# Adafruit_NeoJewel_7.net
KiCad netlist of a schematic drawn in EAGLE
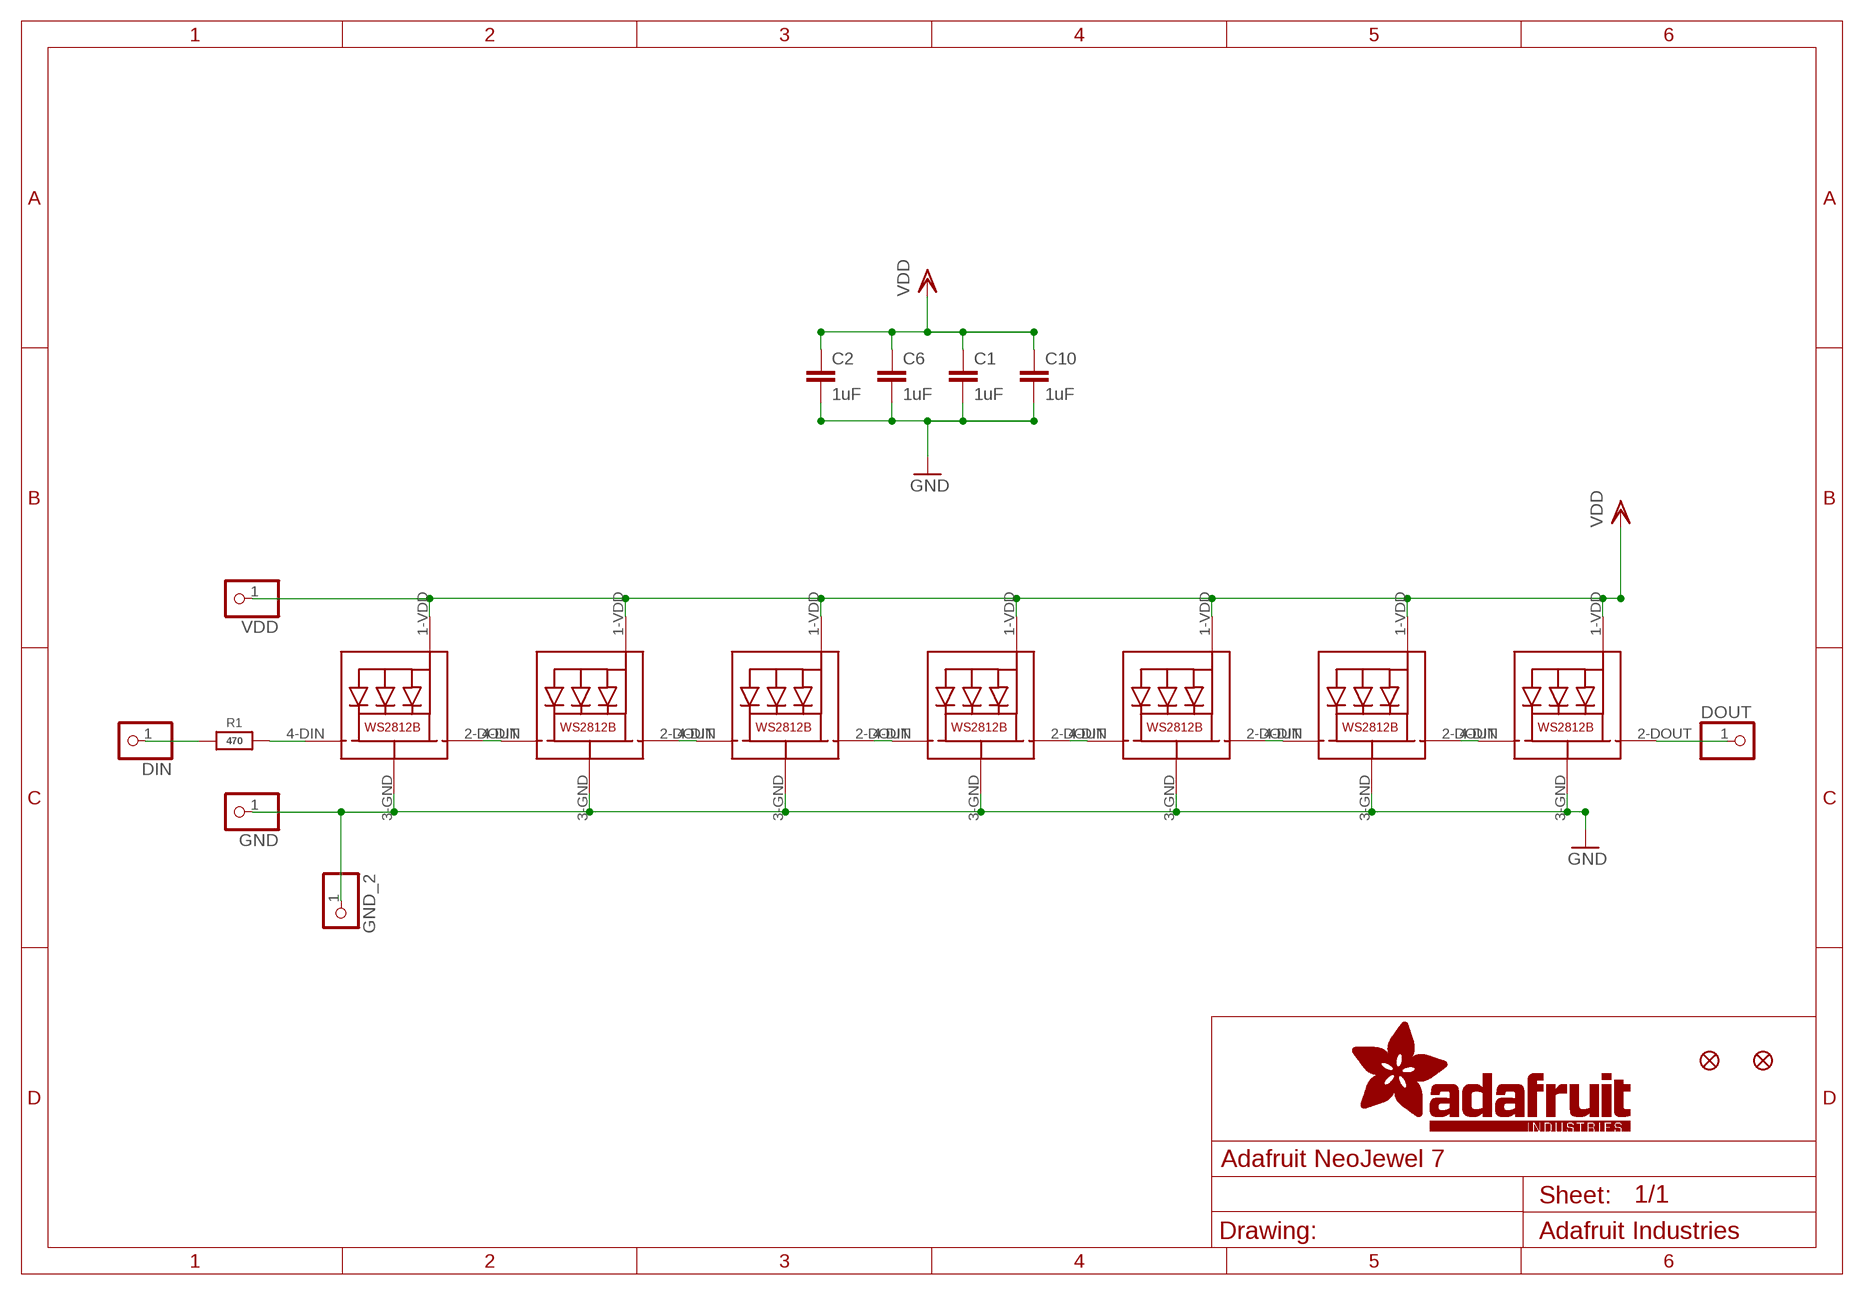
[diagram p0: schematic, sheet 1]

(export (version "E")
  (design (tool "Eeschema 10.0.6"))
  (components
    (comp (ref "C1")
      (value "1uF")
      (footprint "eagle-import:C0603")
      (libsource (lib "eagle-import") (part "C-EUC0603"))
    )
    (comp (ref "C2")
      (value "1uF")
      (footprint "eagle-import:C0603")
      (libsource (lib "eagle-import") (part "C-EUC0603"))
    )
    (comp (ref "C6")
      (value "1uF")
      (footprint "eagle-import:C0603")
      (libsource (lib "eagle-import") (part "C-EUC0603"))
    )
    (comp (ref "C10")
      (value "1uF")
      (footprint "eagle-import:C0603")
      (libsource (lib "eagle-import") (part "C-EUC0603"))
    )
    (comp (ref "DIN")
      (value "PINHD-1X1CB")
      (footprint "eagle-import:1X01-CLEANBIG")
      (libsource (lib "eagle-import") (part "PINHD-1X1CB"))
    )
    (comp (ref "DOUT")
      (value "PINHD-1X1CB")
      (footprint "eagle-import:1X01-CLEANBIG")
      (libsource (lib "eagle-import") (part "PINHD-1X1CB"))
    )
    (comp (ref "FID1")
      (value "FIDUCIAL\"\"")
      (footprint "eagle-import:FIDUCIAL_1MM")
      (libsource (lib "eagle-import") (part "FIDUCIAL{dblquote}{dblquote}"))
    )
    (comp (ref "FID2")
      (value "FIDUCIAL\"\"")
      (footprint "eagle-import:FIDUCIAL_1MM")
      (libsource (lib "eagle-import") (part "FIDUCIAL{dblquote}{dblquote}"))
    )
    (comp (ref "GND")
      (value "PINHD-1X1CB")
      (footprint "eagle-import:1X01-CLEANBIG")
      (libsource (lib "eagle-import") (part "PINHD-1X1CB"))
    )
    (comp (ref "GND_2")
      (value "PINHD-1X1CB")
      (footprint "eagle-import:1X01-CLEANBIG")
      (libsource (lib "eagle-import") (part "PINHD-1X1CB"))
    )
    (comp (ref "LED1")
      (value "WS2812B5050")
      (footprint "eagle-import:WS2812B")
      (libsource (lib "eagle-import") (part "WS2812B5050"))
    )
    (comp (ref "LED2")
      (value "WS2812B5050")
      (footprint "eagle-import:WS2812B")
      (libsource (lib "eagle-import") (part "WS2812B5050"))
    )
    (comp (ref "LED3")
      (value "WS2812B5050")
      (footprint "eagle-import:WS2812B")
      (libsource (lib "eagle-import") (part "WS2812B5050"))
    )
    (comp (ref "LED4")
      (value "WS2812B5050")
      (footprint "eagle-import:WS2812B")
      (libsource (lib "eagle-import") (part "WS2812B5050"))
    )
    (comp (ref "LED5")
      (value "WS2812B5050")
      (footprint "eagle-import:WS2812B")
      (libsource (lib "eagle-import") (part "WS2812B5050"))
    )
    (comp (ref "LED6")
      (value "WS2812B5050")
      (footprint "eagle-import:WS2812B")
      (libsource (lib "eagle-import") (part "WS2812B5050"))
    )
    (comp (ref "LED7")
      (value "WS2812B5050")
      (footprint "eagle-import:WS2812B")
      (libsource (lib "eagle-import") (part "WS2812B5050"))
    )
    (comp (ref "R1")
      (value "470")
      (footprint "eagle-import:0603-NO")
      (libsource (lib "eagle-import") (part "RESISTOR_0603_NOOUT"))
    )
    (comp (ref "VDD")
      (value "PINHD-1X1CB")
      (footprint "eagle-import:1X01-CLEANBIG")
      (libsource (lib "eagle-import") (part "PINHD-1X1CB"))
    )
  )
  (nets
    (net (code "1") (name "GND") (class "Default")
      (node (ref "C1") (pin "2") (pinfunction "2_2") (pintype "passive"))
      (node (ref "C10") (pin "2") (pinfunction "2_2") (pintype "passive"))
      (node (ref "C2") (pin "2") (pinfunction "2_2") (pintype "passive"))
      (node (ref "C6") (pin "2") (pinfunction "2_2") (pintype "passive"))
      (node (ref "GND") (pin "1") (pinfunction "1_1") (pintype "passive"))
      (node (ref "GND_2") (pin "1") (pinfunction "1_1") (pintype "passive"))
      (node (ref "LED1") (pin "3-GND") (pinfunction "GND_3-GND") (pintype "power_in"))
      (node (ref "LED2") (pin "3-GND") (pinfunction "GND_3-GND") (pintype "power_in"))
      (node (ref "LED3") (pin "3-GND") (pinfunction "GND_3-GND") (pintype "power_in"))
      (node (ref "LED4") (pin "3-GND") (pinfunction "GND_3-GND") (pintype "power_in"))
      (node (ref "LED5") (pin "3-GND") (pinfunction "GND_3-GND") (pintype "power_in"))
      (node (ref "LED6") (pin "3-GND") (pinfunction "GND_3-GND") (pintype "power_in"))
      (node (ref "LED7") (pin "3-GND") (pinfunction "GND_3-GND") (pintype "power_in"))
    )
    (net (code "2") (name "Net-(DIN-Pad1)") (class "Default")
      (node (ref "DIN") (pin "1") (pinfunction "1_1") (pintype "passive"))
      (node (ref "R1") (pin "1") (pinfunction "1_1") (pintype "passive"))
    )
    (net (code "3") (name "Net-(LED1-DI)") (class "Default")
      (node (ref "LED1") (pin "4-DIN") (pinfunction "DI_4-DIN") (pintype "input"))
      (node (ref "R1") (pin "2") (pinfunction "2_2") (pintype "passive"))
    )
    (net (code "4") (name "Net-(LED1-DO)") (class "Default")
      (node (ref "LED1") (pin "2-DOUT") (pinfunction "DO_2-DOUT") (pintype "output"))
      (node (ref "LED2") (pin "4-DIN") (pinfunction "DI_4-DIN") (pintype "input"))
    )
    (net (code "5") (name "Net-(LED2-DO)") (class "Default")
      (node (ref "LED2") (pin "2-DOUT") (pinfunction "DO_2-DOUT") (pintype "output"))
      (node (ref "LED3") (pin "4-DIN") (pinfunction "DI_4-DIN") (pintype "input"))
    )
    (net (code "6") (name "Net-(LED3-DO)") (class "Default")
      (node (ref "LED3") (pin "2-DOUT") (pinfunction "DO_2-DOUT") (pintype "output"))
      (node (ref "LED4") (pin "4-DIN") (pinfunction "DI_4-DIN") (pintype "input"))
    )
    (net (code "7") (name "Net-(LED4-DO)") (class "Default")
      (node (ref "LED4") (pin "2-DOUT") (pinfunction "DO_2-DOUT") (pintype "output"))
      (node (ref "LED5") (pin "4-DIN") (pinfunction "DI_4-DIN") (pintype "input"))
    )
    (net (code "8") (name "Net-(LED5-DO)") (class "Default")
      (node (ref "LED5") (pin "2-DOUT") (pinfunction "DO_2-DOUT") (pintype "output"))
      (node (ref "LED6") (pin "4-DIN") (pinfunction "DI_4-DIN") (pintype "input"))
    )
    (net (code "9") (name "Net-(LED6-DO)") (class "Default")
      (node (ref "LED6") (pin "2-DOUT") (pinfunction "DO_2-DOUT") (pintype "output"))
      (node (ref "LED7") (pin "4-DIN") (pinfunction "DI_4-DIN") (pintype "input"))
    )
    (net (code "10") (name "Net-(LED7-DO)") (class "Default")
      (node (ref "DOUT") (pin "1") (pinfunction "1_1") (pintype "passive"))
      (node (ref "LED7") (pin "2-DOUT") (pinfunction "DO_2-DOUT") (pintype "output"))
    )
    (net (code "11") (name "VDD") (class "Default")
      (node (ref "C1") (pin "1") (pinfunction "1_1") (pintype "passive"))
      (node (ref "C10") (pin "1") (pinfunction "1_1") (pintype "passive"))
      (node (ref "C2") (pin "1") (pinfunction "1_1") (pintype "passive"))
      (node (ref "C6") (pin "1") (pinfunction "1_1") (pintype "passive"))
      (node (ref "LED1") (pin "1-VDD") (pinfunction "VDD_1-VDD") (pintype "power_in"))
      (node (ref "LED2") (pin "1-VDD") (pinfunction "VDD_1-VDD") (pintype "power_in"))
      (node (ref "LED3") (pin "1-VDD") (pinfunction "VDD_1-VDD") (pintype "power_in"))
      (node (ref "LED4") (pin "1-VDD") (pinfunction "VDD_1-VDD") (pintype "power_in"))
      (node (ref "LED5") (pin "1-VDD") (pinfunction "VDD_1-VDD") (pintype "power_in"))
      (node (ref "LED6") (pin "1-VDD") (pinfunction "VDD_1-VDD") (pintype "power_in"))
      (node (ref "LED7") (pin "1-VDD") (pinfunction "VDD_1-VDD") (pintype "power_in"))
      (node (ref "VDD") (pin "1") (pinfunction "1_1") (pintype "passive"))
    )
  )
)
